# CC2530-Board.net
KiCad netlist of a schematic drawn in Altium Designer
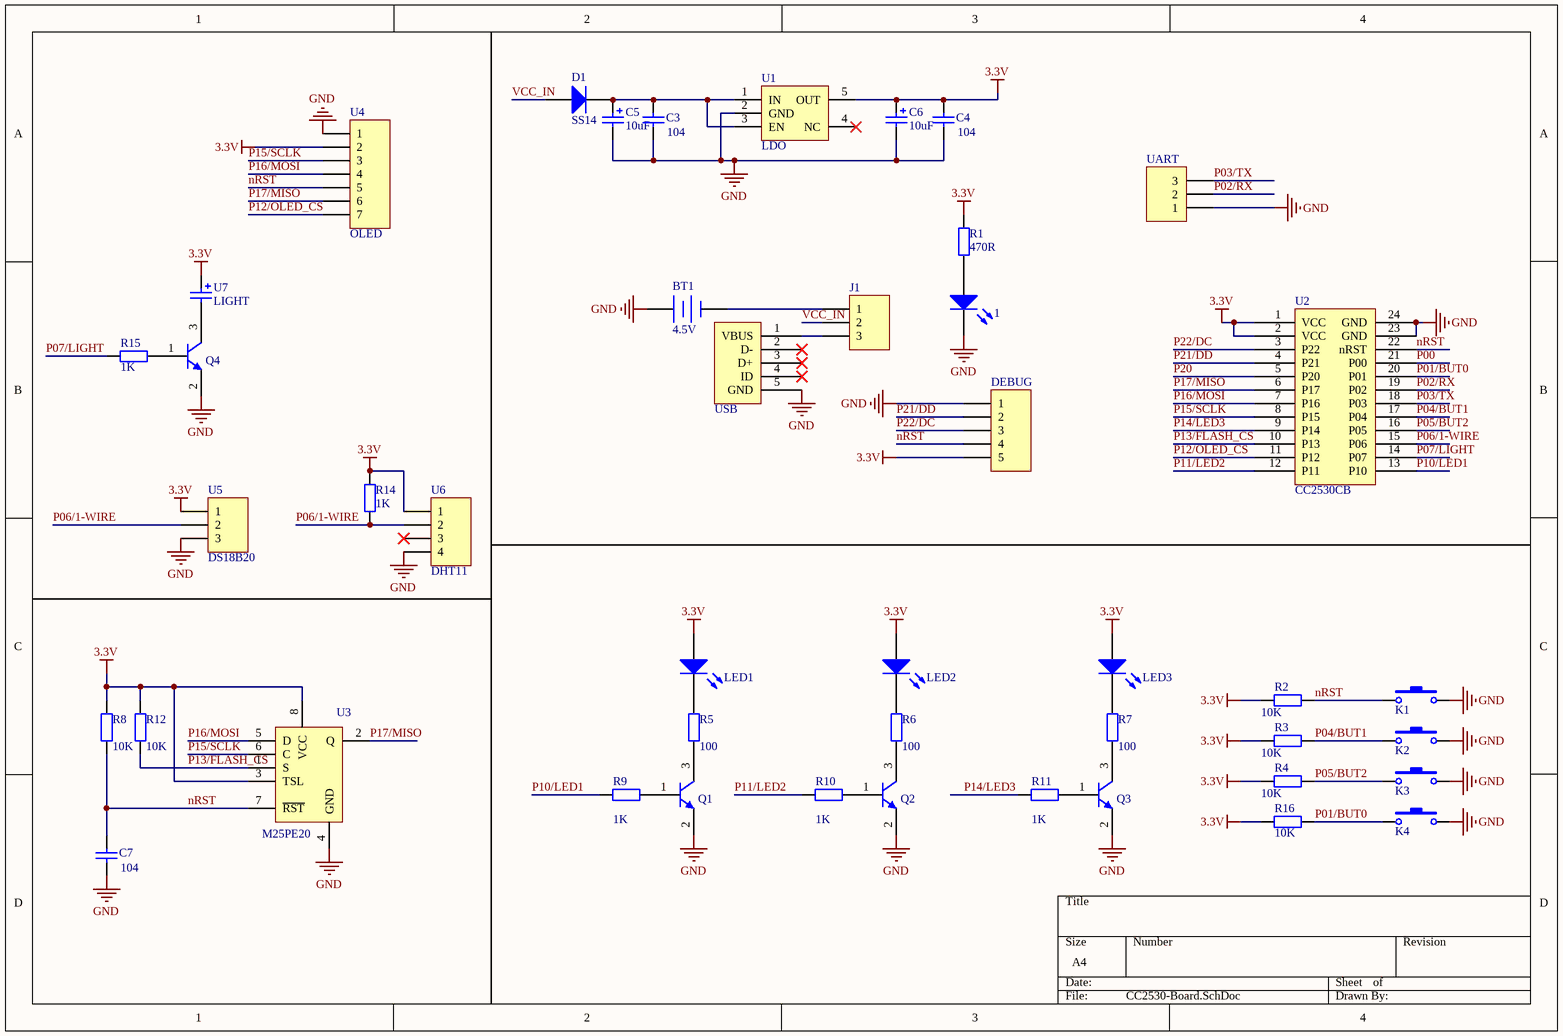
[diagram p0: CC2530-Board.SchDoc]

(export (version "E")
  (design (tool "Eeschema 10.0.6"))
  (components
    (comp (ref "1") (value "LED_SMD") (footprint "0603") (libsource (lib "My_Int_Lib") (part "LED_0805")))
    (comp (ref "2") (value "USB") (footprint "MINI-USB") (libsource (lib "My_Int_Lib") (part "Mini_USB")))
    (comp (ref "BT1")
      (value "4.5V")
      (footprint "BAT-2")
      (description "Multicell Battery")
      (fields (field (name "PUBLISHER") "Altium Limited"))
      (libsource (lib "Miscellaneous Devices") (part "Battery"))
    )
    (comp (ref "C3") (value "104") (footprint "0603") (libsource (lib "My_Int_Lib") (part "C_0805")))
    (comp (ref "C4") (value "104") (footprint "0603") (libsource (lib "My_Int_Lib") (part "C_0805")))
    (comp (ref "C5")
      (value "10uF")
      (footprint "C-1210")
      (description "Polarized Capacitor (Radial)")
      (fields (field (name "PUBLISHER") "Altium Limited"))
      (libsource (lib "My_Int_Lib") (part "Cap Pol"))
    )
    (comp (ref "C6")
      (value "10uF")
      (footprint "C-1210")
      (description "Polarized Capacitor (Radial)")
      (fields (field (name "PUBLISHER") "Altium Limited"))
      (libsource (lib "My_Int_Lib") (part "Cap Pol"))
    )
    (comp (ref "C7") (value "104") (footprint "0603") (libsource (lib "My_Int_Lib") (part "C_0805")))
    (comp (ref "D1")
      (value "SS14")
      (footprint "SS14")
      (description "Default Diode")
      (fields (field (name "PUBLISHER") "Altium Limited"))
      (libsource (lib "Miscellaneous Devices") (part "Diode"))
    )
    (comp (ref "DEBUG")
      (value "~")
      (footprint "HDR1X5")
      (description "Header, 5-Pin")
      (fields (field (name "PUBLISHER") "Altium Limited"))
      (libsource (lib "Miscellaneous Connectors") (part "Header 5"))
    )
    (comp (ref "J1")
      (value "Header 3")
      (footprint "Key-7Pin")
      (description "Header, 3-Pin")
      (fields (field (name "PUBLISHER") "Altium Limited"))
      (libsource (lib "") (part "Header 3_1"))
    )
    (comp (ref "K1")
      (value "Mini-Key")
      (footprint "MINI-KEY")
      (libsource (lib "My_Int_Lib") (part "Mini-Key"))
    )
    (comp (ref "K2")
      (value "Mini-Key")
      (footprint "MINI-KEY")
      (libsource (lib "My_Int_Lib") (part "Mini-Key"))
    )
    (comp (ref "K3")
      (value "Mini-Key")
      (footprint "MINI-KEY")
      (libsource (lib "My_Int_Lib") (part "Mini-Key"))
    )
    (comp (ref "K4")
      (value "Mini-Key")
      (footprint "MINI-KEY")
      (libsource (lib "My_Int_Lib") (part "Mini-Key"))
    )
    (comp (ref "LED1") (value "LED_SMD") (footprint "0603") (libsource (lib "My_Int_Lib") (part "LED_0805")))
    (comp (ref "LED2") (value "LED_SMD") (footprint "0603") (libsource (lib "My_Int_Lib") (part "LED_0805")))
    (comp (ref "LED3") (value "LED_SMD") (footprint "0603") (libsource (lib "My_Int_Lib") (part "LED_0805")))
    (comp (ref "Q1")
      (value "NPN_SMD")
      (footprint "SOT23-3")
      (description "NPN Bipolar Transistor")
      (fields (field (name "PUBLISHER") "Altium Limited"))
      (libsource (lib "My_Int_Lib") (part "NPN_SMD"))
    )
    (comp (ref "Q2")
      (value "NPN_SMD")
      (footprint "SOT23-3")
      (description "NPN Bipolar Transistor")
      (fields (field (name "PUBLISHER") "Altium Limited"))
      (libsource (lib "My_Int_Lib") (part "NPN_SMD"))
    )
    (comp (ref "Q3")
      (value "NPN_SMD")
      (footprint "SOT23-3")
      (description "NPN Bipolar Transistor")
      (fields (field (name "PUBLISHER") "Altium Limited"))
      (libsource (lib "My_Int_Lib") (part "NPN_SMD"))
    )
    (comp (ref "Q4")
      (value "NPN_SMD")
      (footprint "SOT23-3")
      (description "NPN Bipolar Transistor")
      (fields (field (name "PUBLISHER") "Altium Limited"))
      (libsource (lib "My_Int_Lib") (part "NPN_SMD"))
    )
    (comp (ref "R1") (value "470R") (footprint "0603") (libsource (lib "") (part "R_0805_1")))
    (comp (ref "R2") (value "10K") (footprint "0603") (libsource (lib "My_Int_Lib") (part "R_0805")))
    (comp (ref "R3") (value "10K") (footprint "0603") (libsource (lib "My_Int_Lib") (part "R_0805")))
    (comp (ref "R4") (value "10K") (footprint "0603") (libsource (lib "My_Int_Lib") (part "R_0805")))
    (comp (ref "R5") (value "100") (footprint "0603") (libsource (lib "") (part "R_0805_1")))
    (comp (ref "R6") (value "100") (footprint "0603") (libsource (lib "") (part "R_0805_1")))
    (comp (ref "R7") (value "100") (footprint "0603") (libsource (lib "") (part "R_0805_1")))
    (comp (ref "R8") (value "10K") (footprint "0603") (libsource (lib "") (part "R_0805_1")))
    (comp (ref "R9") (value "1K") (footprint "0603") (libsource (lib "") (part "R_0805_2")))
    (comp (ref "R10") (value "1K") (footprint "0603") (libsource (lib "") (part "R_0805_2")))
    (comp (ref "R11") (value "1K") (footprint "0603") (libsource (lib "") (part "R_0805_2")))
    (comp (ref "R12") (value "10K") (footprint "0603") (libsource (lib "") (part "R_0805_1")))
    (comp (ref "R14") (value "1K") (footprint "0603") (libsource (lib "") (part "R_0805_1")))
    (comp (ref "R15") (value "1K") (footprint "0603") (libsource (lib "My_Int_Lib") (part "R_0805")))
    (comp (ref "R16") (value "10K") (footprint "0603") (libsource (lib "My_Int_Lib") (part "R_0805")))
    (comp (ref "U1") (value "LDO") (footprint "SOT23-5") (libsource (lib "BOARD") (part "LDO-3.3")))
    (comp (ref "U2") (value "CC2530CB") (footprint "CC2530CB") (libsource (lib "BOARD") (part "CC2530CB")))
    (comp (ref "U3") (value "M25PE20") (footprint "M25PE20") (libsource (lib "BOARD") (part "M25PE20")))
    (comp (ref "U4")
      (value "OLED")
      (footprint "OLED-0.96")
      (description "Header, 7-Pin")
      (fields (field (name "PUBLISHER") "Altium Limited"))
      (libsource (lib "Miscellaneous Connectors") (part "Header 7"))
    )
    (comp (ref "U5")
      (value "DS18B20")
      (footprint "MHDR1X3")
      (description "Header, 3-Pin")
      (fields (field (name "PUBLISHER") "Altium Limited"))
      (libsource (lib "Miscellaneous Connectors") (part "MHDR1X3"))
    )
    (comp (ref "U6")
      (value "DHT11")
      (footprint "HDR1X4")
      (description "Header, 4-Pin")
      (fields (field (name "PUBLISHER") "Altium Limited"))
      (libsource (lib "Miscellaneous Connectors") (part "Header 4"))
    )
    (comp (ref "U7")
      (value "LIGHT")
      (footprint "C-1210")
      (description "Polarized Capacitor (Radial)")
      (fields (field (name "PUBLISHER") "Altium Limited"))
      (libsource (lib "My_Int_Lib") (part "Cap Pol"))
    )
    (comp (ref "UART")
      (value "Header 3")
      (footprint "HDR1X3")
      (description "Header, 3-Pin")
      (fields (field (name "PUBLISHER") "Altium Limited"))
      (libsource (lib "Miscellaneous Connectors") (part "Header 3"))
    )
  )
  (nets
    (net (code "1") (name "/P00") (class "Default")
      (node (ref "U2") (pin "21") (pinfunction "P00_21") (pintype "passive"))
    )
    (net (code "2") (name "/P01{slash}BUT0") (class "Default")
      (node (ref "K4") (pin "1") (pinfunction "1_1") (pintype "passive"))
      (node (ref "R16") (pin "1") (pinfunction "1_1") (pintype "passive"))
      (node (ref "U2") (pin "20") (pinfunction "P01_20") (pintype "passive"))
    )
    (net (code "3") (name "/P02{slash}RX") (class "Default")
      (node (ref "U2") (pin "19") (pinfunction "P02_19") (pintype "passive"))
      (node (ref "UART") (pin "2") (pinfunction "2_2") (pintype "passive"))
    )
    (net (code "4") (name "/P03{slash}TX") (class "Default")
      (node (ref "U2") (pin "18") (pinfunction "P03_18") (pintype "passive"))
      (node (ref "UART") (pin "3") (pinfunction "3_3") (pintype "passive"))
    )
    (net (code "5") (name "/P04{slash}BUT1") (class "Default")
      (node (ref "K2") (pin "1") (pinfunction "1_1") (pintype "passive"))
      (node (ref "R3") (pin "1") (pinfunction "1_1") (pintype "passive"))
      (node (ref "U2") (pin "17") (pinfunction "P04_17") (pintype "passive"))
    )
    (net (code "6") (name "/P05{slash}BUT2") (class "Default")
      (node (ref "K3") (pin "1") (pinfunction "1_1") (pintype "passive"))
      (node (ref "R4") (pin "1") (pinfunction "1_1") (pintype "passive"))
      (node (ref "U2") (pin "16") (pinfunction "P05_16") (pintype "passive"))
    )
    (net (code "7") (name "/P06{slash}1-WIRE") (class "Default")
      (node (ref "R14") (pin "1") (pinfunction "1_1") (pintype "passive"))
      (node (ref "U2") (pin "15") (pinfunction "P06_15") (pintype "passive"))
      (node (ref "U5") (pin "2") (pinfunction "2_2") (pintype "passive"))
      (node (ref "U6") (pin "2") (pinfunction "2_2") (pintype "passive"))
    )
    (net (code "8") (name "/P07{slash}LIGHT") (class "Default")
      (node (ref "R15") (pin "2") (pinfunction "2_2") (pintype "passive"))
      (node (ref "U2") (pin "14") (pinfunction "P07_14") (pintype "passive"))
    )
    (net (code "9") (name "/P10{slash}LED1") (class "Default")
      (node (ref "R9") (pin "1") (pinfunction "1_1") (pintype "passive"))
      (node (ref "U2") (pin "13") (pinfunction "P10_13") (pintype "passive"))
    )
    (net (code "10") (name "/P11{slash}LED2") (class "Default")
      (node (ref "R10") (pin "1") (pinfunction "1_1") (pintype "passive"))
      (node (ref "U2") (pin "12") (pinfunction "P11_12") (pintype "passive"))
    )
    (net (code "11") (name "/P12{slash}OLED_CS") (class "Default")
      (node (ref "U2") (pin "11") (pinfunction "P12_11") (pintype "passive"))
      (node (ref "U4") (pin "7") (pinfunction "7_7") (pintype "passive"))
    )
    (net (code "12") (name "/P13{slash}FLASH_CS") (class "Default")
      (node (ref "R12") (pin "1") (pinfunction "1_1") (pintype "passive"))
      (node (ref "U2") (pin "10") (pinfunction "P13_10") (pintype "passive"))
      (node (ref "U3") (pin "1") (pinfunction "S_1") (pintype "passive"))
    )
    (net (code "13") (name "/P14{slash}LED3") (class "Default")
      (node (ref "R11") (pin "1") (pinfunction "1_1") (pintype "passive"))
      (node (ref "U2") (pin "9") (pinfunction "P14_9") (pintype "passive"))
    )
    (net (code "14") (name "/P15{slash}SCLK") (class "Default")
      (node (ref "U2") (pin "8") (pinfunction "P15_8") (pintype "passive"))
      (node (ref "U3") (pin "6") (pinfunction "C_6") (pintype "passive"))
      (node (ref "U4") (pin "3") (pinfunction "3_3") (pintype "passive"))
    )
    (net (code "15") (name "/P16{slash}MOSI") (class "Default")
      (node (ref "U2") (pin "7") (pinfunction "P16_7") (pintype "passive"))
      (node (ref "U3") (pin "5") (pinfunction "D_5") (pintype "passive"))
      (node (ref "U4") (pin "4") (pinfunction "4_4") (pintype "passive"))
    )
    (net (code "16") (name "/P17{slash}MISO") (class "Default")
      (node (ref "U2") (pin "6") (pinfunction "P17_6") (pintype "passive"))
      (node (ref "U3") (pin "2") (pinfunction "Q_2") (pintype "passive"))
      (node (ref "U4") (pin "6") (pinfunction "6_6") (pintype "passive"))
    )
    (net (code "17") (name "/P20") (class "Default")
      (node (ref "U2") (pin "5") (pinfunction "P20_5") (pintype "passive"))
    )
    (net (code "18") (name "/P21{slash}DD") (class "Default")
      (node (ref "DEBUG") (pin "2") (pinfunction "2_2") (pintype "passive"))
      (node (ref "U2") (pin "4") (pinfunction "P21_4") (pintype "passive"))
    )
    (net (code "19") (name "/P22{slash}DC") (class "Default")
      (node (ref "DEBUG") (pin "3") (pinfunction "3_3") (pintype "passive"))
      (node (ref "U2") (pin "3") (pinfunction "P22_3") (pintype "passive"))
    )
    (net (code "20") (name "/VCC_IN") (class "Default")
      (node (ref "D1") (pin "1") (pinfunction "A_1") (pintype "passive"))
      (node (ref "J1") (pin "2") (pinfunction "2_2") (pintype "passive"))
    )
    (net (code "21") (name "/nRST") (class "Default")
      (node (ref "C7") (pin "2") (pinfunction "2_2") (pintype "passive"))
      (node (ref "DEBUG") (pin "4") (pinfunction "4_4") (pintype "passive"))
      (node (ref "K1") (pin "1") (pinfunction "1_1") (pintype "passive"))
      (node (ref "R2") (pin "1") (pinfunction "1_1") (pintype "passive"))
      (node (ref "R8") (pin "1") (pinfunction "1_1") (pintype "passive"))
      (node (ref "U2") (pin "22") (pinfunction "nRST_22") (pintype "passive"))
      (node (ref "U3") (pin "7") (pinfunction "~{RST}_7") (pintype "passive"))
      (node (ref "U4") (pin "5") (pinfunction "5_5") (pintype "passive"))
    )
    (net (code "22") (name "3.3V") (class "Default")
      (node (ref "C4") (pin "2") (pinfunction "2_2") (pintype "passive"))
      (node (ref "C6") (pin "1") (pinfunction "1_1") (pintype "passive"))
      (node (ref "DEBUG") (pin "5") (pinfunction "5_5") (pintype "passive"))
      (node (ref "LED1") (pin "1") (pinfunction "A_1") (pintype "passive"))
      (node (ref "LED2") (pin "1") (pinfunction "A_1") (pintype "passive"))
      (node (ref "LED3") (pin "1") (pinfunction "A_1") (pintype "passive"))
      (node (ref "R1") (pin "2") (pinfunction "2_2") (pintype "passive"))
      (node (ref "R12") (pin "2") (pinfunction "2_2") (pintype "passive"))
      (node (ref "R14") (pin "2") (pinfunction "2_2") (pintype "passive"))
      (node (ref "R16") (pin "2") (pinfunction "2_2") (pintype "passive"))
      (node (ref "R2") (pin "2") (pinfunction "2_2") (pintype "passive"))
      (node (ref "R3") (pin "2") (pinfunction "2_2") (pintype "passive"))
      (node (ref "R4") (pin "2") (pinfunction "2_2") (pintype "passive"))
      (node (ref "R8") (pin "2") (pinfunction "2_2") (pintype "passive"))
      (node (ref "U1") (pin "5") (pinfunction "OUT_5") (pintype "passive"))
      (node (ref "U2") (pin "1") (pinfunction "VCC_1") (pintype "passive"))
      (node (ref "U2") (pin "2") (pinfunction "VCC_2") (pintype "passive"))
      (node (ref "U3") (pin "3") (pinfunction "TSL_3") (pintype "passive"))
      (node (ref "U3") (pin "8") (pinfunction "VCC_8") (pintype "passive"))
      (node (ref "U4") (pin "2") (pinfunction "2_2") (pintype "passive"))
      (node (ref "U5") (pin "1") (pinfunction "1_1") (pintype "passive"))
      (node (ref "U6") (pin "1") (pinfunction "1_1") (pintype "passive"))
      (node (ref "U7") (pin "1") (pinfunction "1_1") (pintype "passive"))
    )
    (net (code "23") (name "GND") (class "Default")
      (node (ref "1") (pin "2") (pinfunction "K_2") (pintype "passive"))
      (node (ref "2") (pin "5") (pinfunction "GND_5") (pintype "passive"))
      (node (ref "BT1") (pin "1") (pinfunction "+_1") (pintype "passive"))
      (node (ref "C3") (pin "1") (pinfunction "1_1") (pintype "passive"))
      (node (ref "C4") (pin "1") (pinfunction "1_1") (pintype "passive"))
      (node (ref "C5") (pin "2") (pinfunction "2_2") (pintype "passive"))
      (node (ref "C6") (pin "2") (pinfunction "2_2") (pintype "passive"))
      (node (ref "C7") (pin "1") (pinfunction "1_1") (pintype "passive"))
      (node (ref "DEBUG") (pin "1") (pinfunction "1_1") (pintype "passive"))
      (node (ref "K1") (pin "2") (pinfunction "2_2") (pintype "passive"))
      (node (ref "K2") (pin "2") (pinfunction "2_2") (pintype "passive"))
      (node (ref "K3") (pin "2") (pinfunction "2_2") (pintype "passive"))
      (node (ref "K4") (pin "2") (pinfunction "2_2") (pintype "passive"))
      (node (ref "Q1") (pin "2") (pinfunction "E_2") (pintype "passive"))
      (node (ref "Q2") (pin "2") (pinfunction "E_2") (pintype "passive"))
      (node (ref "Q3") (pin "2") (pinfunction "E_2") (pintype "passive"))
      (node (ref "Q4") (pin "2") (pinfunction "E_2") (pintype "passive"))
      (node (ref "U1") (pin "2") (pinfunction "GND_2") (pintype "passive"))
      (node (ref "U2") (pin "23") (pinfunction "GND_23") (pintype "passive"))
      (node (ref "U2") (pin "24") (pinfunction "GND_24") (pintype "passive"))
      (node (ref "U3") (pin "4") (pinfunction "GND_4") (pintype "passive"))
      (node (ref "U4") (pin "1") (pinfunction "1_1") (pintype "passive"))
      (node (ref "U5") (pin "3") (pinfunction "3_3") (pintype "passive"))
      (node (ref "U6") (pin "4") (pinfunction "4_4") (pintype "passive"))
      (node (ref "UART") (pin "1") (pinfunction "1_1") (pintype "passive"))
    )
    (net (code "24") (name "Net-(1-A)") (class "Default")
      (node (ref "1") (pin "1") (pinfunction "A_1") (pintype "passive"))
      (node (ref "R1") (pin "1") (pinfunction "1_1") (pintype "passive"))
    )
    (net (code "25") (name "Net-(2-VBUS)") (class "Default")
      (node (ref "2") (pin "1") (pinfunction "VBUS_1") (pintype "passive"))
      (node (ref "J1") (pin "3") (pinfunction "3_3") (pintype "passive"))
    )
    (net (code "26") (name "Net-(BT1--)") (class "Default")
      (node (ref "BT1") (pin "2") (pinfunction "-_2") (pintype "passive"))
      (node (ref "J1") (pin "1") (pinfunction "1_1") (pintype "passive"))
    )
    (net (code "27") (name "Net-(D1-K)") (class "Default")
      (node (ref "C3") (pin "2") (pinfunction "2_2") (pintype "passive"))
      (node (ref "C5") (pin "1") (pinfunction "1_1") (pintype "passive"))
      (node (ref "D1") (pin "2") (pinfunction "K_2") (pintype "passive"))
      (node (ref "U1") (pin "1") (pinfunction "IN_1") (pintype "passive"))
      (node (ref "U1") (pin "3") (pinfunction "EN_3") (pintype "passive"))
    )
    (net (code "28") (name "Net-(LED1-K)") (class "Default")
      (node (ref "LED1") (pin "2") (pinfunction "K_2") (pintype "passive"))
      (node (ref "R5") (pin "2") (pinfunction "2_2") (pintype "passive"))
    )
    (net (code "29") (name "Net-(LED2-K)") (class "Default")
      (node (ref "LED2") (pin "2") (pinfunction "K_2") (pintype "passive"))
      (node (ref "R6") (pin "2") (pinfunction "2_2") (pintype "passive"))
    )
    (net (code "30") (name "Net-(LED3-K)") (class "Default")
      (node (ref "LED3") (pin "2") (pinfunction "K_2") (pintype "passive"))
      (node (ref "R7") (pin "2") (pinfunction "2_2") (pintype "passive"))
    )
    (net (code "31") (name "Net-(Q1-B)") (class "Default")
      (node (ref "Q1") (pin "1") (pinfunction "B_1") (pintype "passive"))
      (node (ref "R9") (pin "2") (pinfunction "2_2") (pintype "passive"))
    )
    (net (code "32") (name "Net-(Q1-C)") (class "Default")
      (node (ref "Q1") (pin "3") (pinfunction "C_3") (pintype "passive"))
      (node (ref "R5") (pin "1") (pinfunction "1_1") (pintype "passive"))
    )
    (net (code "33") (name "Net-(Q2-B)") (class "Default")
      (node (ref "Q2") (pin "1") (pinfunction "B_1") (pintype "passive"))
      (node (ref "R10") (pin "2") (pinfunction "2_2") (pintype "passive"))
    )
    (net (code "34") (name "Net-(Q2-C)") (class "Default")
      (node (ref "Q2") (pin "3") (pinfunction "C_3") (pintype "passive"))
      (node (ref "R6") (pin "1") (pinfunction "1_1") (pintype "passive"))
    )
    (net (code "35") (name "Net-(Q3-B)") (class "Default")
      (node (ref "Q3") (pin "1") (pinfunction "B_1") (pintype "passive"))
      (node (ref "R11") (pin "2") (pinfunction "2_2") (pintype "passive"))
    )
    (net (code "36") (name "Net-(Q3-C)") (class "Default")
      (node (ref "Q3") (pin "3") (pinfunction "C_3") (pintype "passive"))
      (node (ref "R7") (pin "1") (pinfunction "1_1") (pintype "passive"))
    )
    (net (code "37") (name "Net-(Q4-B)") (class "Default")
      (node (ref "Q4") (pin "1") (pinfunction "B_1") (pintype "passive"))
      (node (ref "R15") (pin "1") (pinfunction "1_1") (pintype "passive"))
    )
    (net (code "38") (name "Net-(Q4-C)") (class "Default")
      (node (ref "Q4") (pin "3") (pinfunction "C_3") (pintype "passive"))
      (node (ref "U7") (pin "2") (pinfunction "2_2") (pintype "passive"))
    )
    (net (code "39") (name "unconnected-(2-D+-Pad3)") (class "Default")
      (node (ref "2") (pin "3") (pinfunction "D+_3") (pintype "passive+no_connect"))
    )
    (net (code "40") (name "unconnected-(2-D--Pad2)") (class "Default")
      (node (ref "2") (pin "2") (pinfunction "D-_2") (pintype "passive+no_connect"))
    )
    (net (code "41") (name "unconnected-(2-ID-Pad4)") (class "Default")
      (node (ref "2") (pin "4") (pinfunction "ID_4") (pintype "passive+no_connect"))
    )
    (net (code "42") (name "unconnected-(U1-NC-Pad4)") (class "Default")
      (node (ref "U1") (pin "4") (pinfunction "NC_4") (pintype "passive+no_connect"))
    )
    (net (code "43") (name "unconnected-(U6-Pad3)") (class "Default")
      (node (ref "U6") (pin "3") (pinfunction "3_3") (pintype "passive+no_connect"))
    )
  )
)
